# ltc2400_adc_module.net
KiCad netlist of a schematic drawn in EAGLE
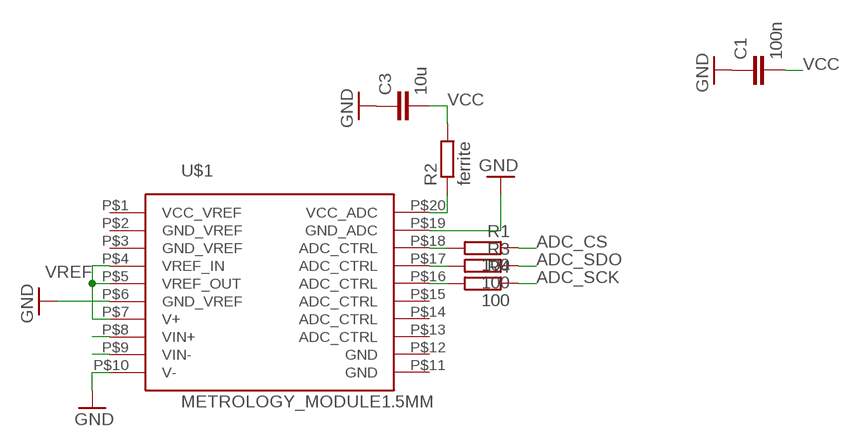
[diagram p0: schematic, sheet 1]

(export (version "E")
  (design (tool "Eeschema 10.0.6"))
  (components
    (comp (ref "C1")
      (value "100n")
      (footprint "eagle-import:C0603")
      (libsource (lib "eagle-import") (part "C-EUC0603"))
    )
    (comp (ref "C3")
      (value "10u")
      (footprint "eagle-import:C0805")
      (libsource (lib "eagle-import") (part "C-EUC0805"))
    )
    (comp (ref "R1")
      (value "100")
      (footprint "eagle-import:R0603")
      (libsource (lib "eagle-import") (part "R-EU_R0603"))
    )
    (comp (ref "R2")
      (value "ferrite")
      (footprint "eagle-import:R0805")
      (libsource (lib "eagle-import") (part "R-EU_R0805"))
    )
    (comp (ref "R3")
      (value "100")
      (footprint "eagle-import:R0603")
      (libsource (lib "eagle-import") (part "R-EU_R0603"))
    )
    (comp (ref "R4")
      (value "100")
      (footprint "eagle-import:R0603")
      (libsource (lib "eagle-import") (part "R-EU_R0603"))
    )
    (comp (ref "U$1")
      (value "METROLOGY_MODULE1.5MM")
      (footprint "eagle-import:METROLOGY_MODULE_1.5MM_HOLE")
      (libsource (lib "eagle-import") (part "METROLOGY_MODULE1.5MM"))
    )
  )
  (nets
    (net (code "1") (name "/ADC_CS") (class "Default")
      (node (ref "R1") (pin "1") (pinfunction "1_1") (pintype "passive"))
    )
    (net (code "2") (name "/ADC_SCK") (class "Default")
      (node (ref "R4") (pin "1") (pinfunction "1_1") (pintype "passive"))
    )
    (net (code "3") (name "/ADC_SDO") (class "Default")
      (node (ref "R3") (pin "1") (pinfunction "1_1") (pintype "passive"))
    )
    (net (code "4") (name "/VCC") (class "Default")
      (node (ref "C1") (pin "2") (pinfunction "2_2") (pintype "passive"))
      (node (ref "C3") (pin "2") (pinfunction "2_2") (pintype "passive"))
      (node (ref "R2") (pin "2") (pinfunction "2_2") (pintype "passive"))
    )
    (net (code "5") (name "/VREF") (class "Default")
      (node (ref "U$1") (pin "P$4") (pinfunction "VREF_IN_P$4") (pintype "bidirectional"))
      (node (ref "U$1") (pin "P$5") (pinfunction "VREF_OUT_P$5") (pintype "bidirectional"))
      (node (ref "U$1") (pin "P$7") (pinfunction "V+_P$7") (pintype "bidirectional"))
    )
    (net (code "6") (name "GND") (class "Default")
      (node (ref "C1") (pin "1") (pinfunction "1_1") (pintype "passive"))
      (node (ref "C3") (pin "1") (pinfunction "1_1") (pintype "passive"))
      (node (ref "U$1") (pin "P$10") (pinfunction "V-_P$10") (pintype "bidirectional"))
      (node (ref "U$1") (pin "P$19") (pinfunction "GND_ADC_P$19") (pintype "bidirectional"))
      (node (ref "U$1") (pin "P$6") (pinfunction "GND_VREF_P$6") (pintype "bidirectional"))
    )
    (net (code "7") (name "Net-(R1-Pad2)") (class "Default")
      (node (ref "R1") (pin "2") (pinfunction "2_2") (pintype "passive"))
      (node (ref "U$1") (pin "P$18") (pinfunction "ADC_CTRL_P$18") (pintype "bidirectional"))
    )
    (net (code "8") (name "Net-(R3-Pad2)") (class "Default")
      (node (ref "R3") (pin "2") (pinfunction "2_2") (pintype "passive"))
      (node (ref "U$1") (pin "P$17") (pinfunction "ADC_CTRL_P$17") (pintype "bidirectional"))
    )
    (net (code "9") (name "Net-(R4-Pad2)") (class "Default")
      (node (ref "R4") (pin "2") (pinfunction "2_2") (pintype "passive"))
      (node (ref "U$1") (pin "P$16") (pinfunction "ADC_CTRL_P$16") (pintype "bidirectional"))
    )
    (net (code "10") (name "Net-(U$1-VCC_ADC)") (class "Default")
      (node (ref "R2") (pin "1") (pinfunction "1_1") (pintype "passive"))
      (node (ref "U$1") (pin "P$20") (pinfunction "VCC_ADC_P$20") (pintype "bidirectional"))
    )
    (net (code "11") (name "unconnected-(U$1-ADC_CTRL-PadP$13)") (class "Default")
      (node (ref "U$1") (pin "P$13") (pinfunction "ADC_CTRL_P$13") (pintype "bidirectional"))
    )
    (net (code "12") (name "unconnected-(U$1-ADC_CTRL-PadP$14)") (class "Default")
      (node (ref "U$1") (pin "P$14") (pinfunction "ADC_CTRL_P$14") (pintype "bidirectional"))
    )
    (net (code "13") (name "unconnected-(U$1-ADC_CTRL-PadP$15)") (class "Default")
      (node (ref "U$1") (pin "P$15") (pinfunction "ADC_CTRL_P$15") (pintype "bidirectional"))
    )
    (net (code "14") (name "unconnected-(U$1-GND-PadP$11)") (class "Default")
      (node (ref "U$1") (pin "P$11") (pinfunction "GND_P$11") (pintype "bidirectional"))
    )
    (net (code "15") (name "unconnected-(U$1-GND-PadP$12)") (class "Default")
      (node (ref "U$1") (pin "P$12") (pinfunction "GND_P$12") (pintype "bidirectional"))
    )
    (net (code "16") (name "unconnected-(U$1-GND_VREF-PadP$2)") (class "Default")
      (node (ref "U$1") (pin "P$2") (pinfunction "GND_VREF_P$2") (pintype "bidirectional"))
    )
    (net (code "17") (name "unconnected-(U$1-GND_VREF-PadP$3)") (class "Default")
      (node (ref "U$1") (pin "P$3") (pinfunction "GND_VREF_P$3") (pintype "bidirectional"))
    )
    (net (code "18") (name "unconnected-(U$1-VCC_VREF-PadP$1)") (class "Default")
      (node (ref "U$1") (pin "P$1") (pinfunction "VCC_VREF_P$1") (pintype "bidirectional"))
    )
    (net (code "19") (name "unconnected-(U$1-VIN+-PadP$8)") (class "Default")
      (node (ref "U$1") (pin "P$8") (pinfunction "VIN+_P$8") (pintype "bidirectional"))
    )
    (net (code "20") (name "unconnected-(U$1-VIN--PadP$9)") (class "Default")
      (node (ref "U$1") (pin "P$9") (pinfunction "VIN-_P$9") (pintype "bidirectional"))
    )
  )
)
